# Sprite_CC1310_Development.net
KiCad netlist of a schematic drawn in EAGLE
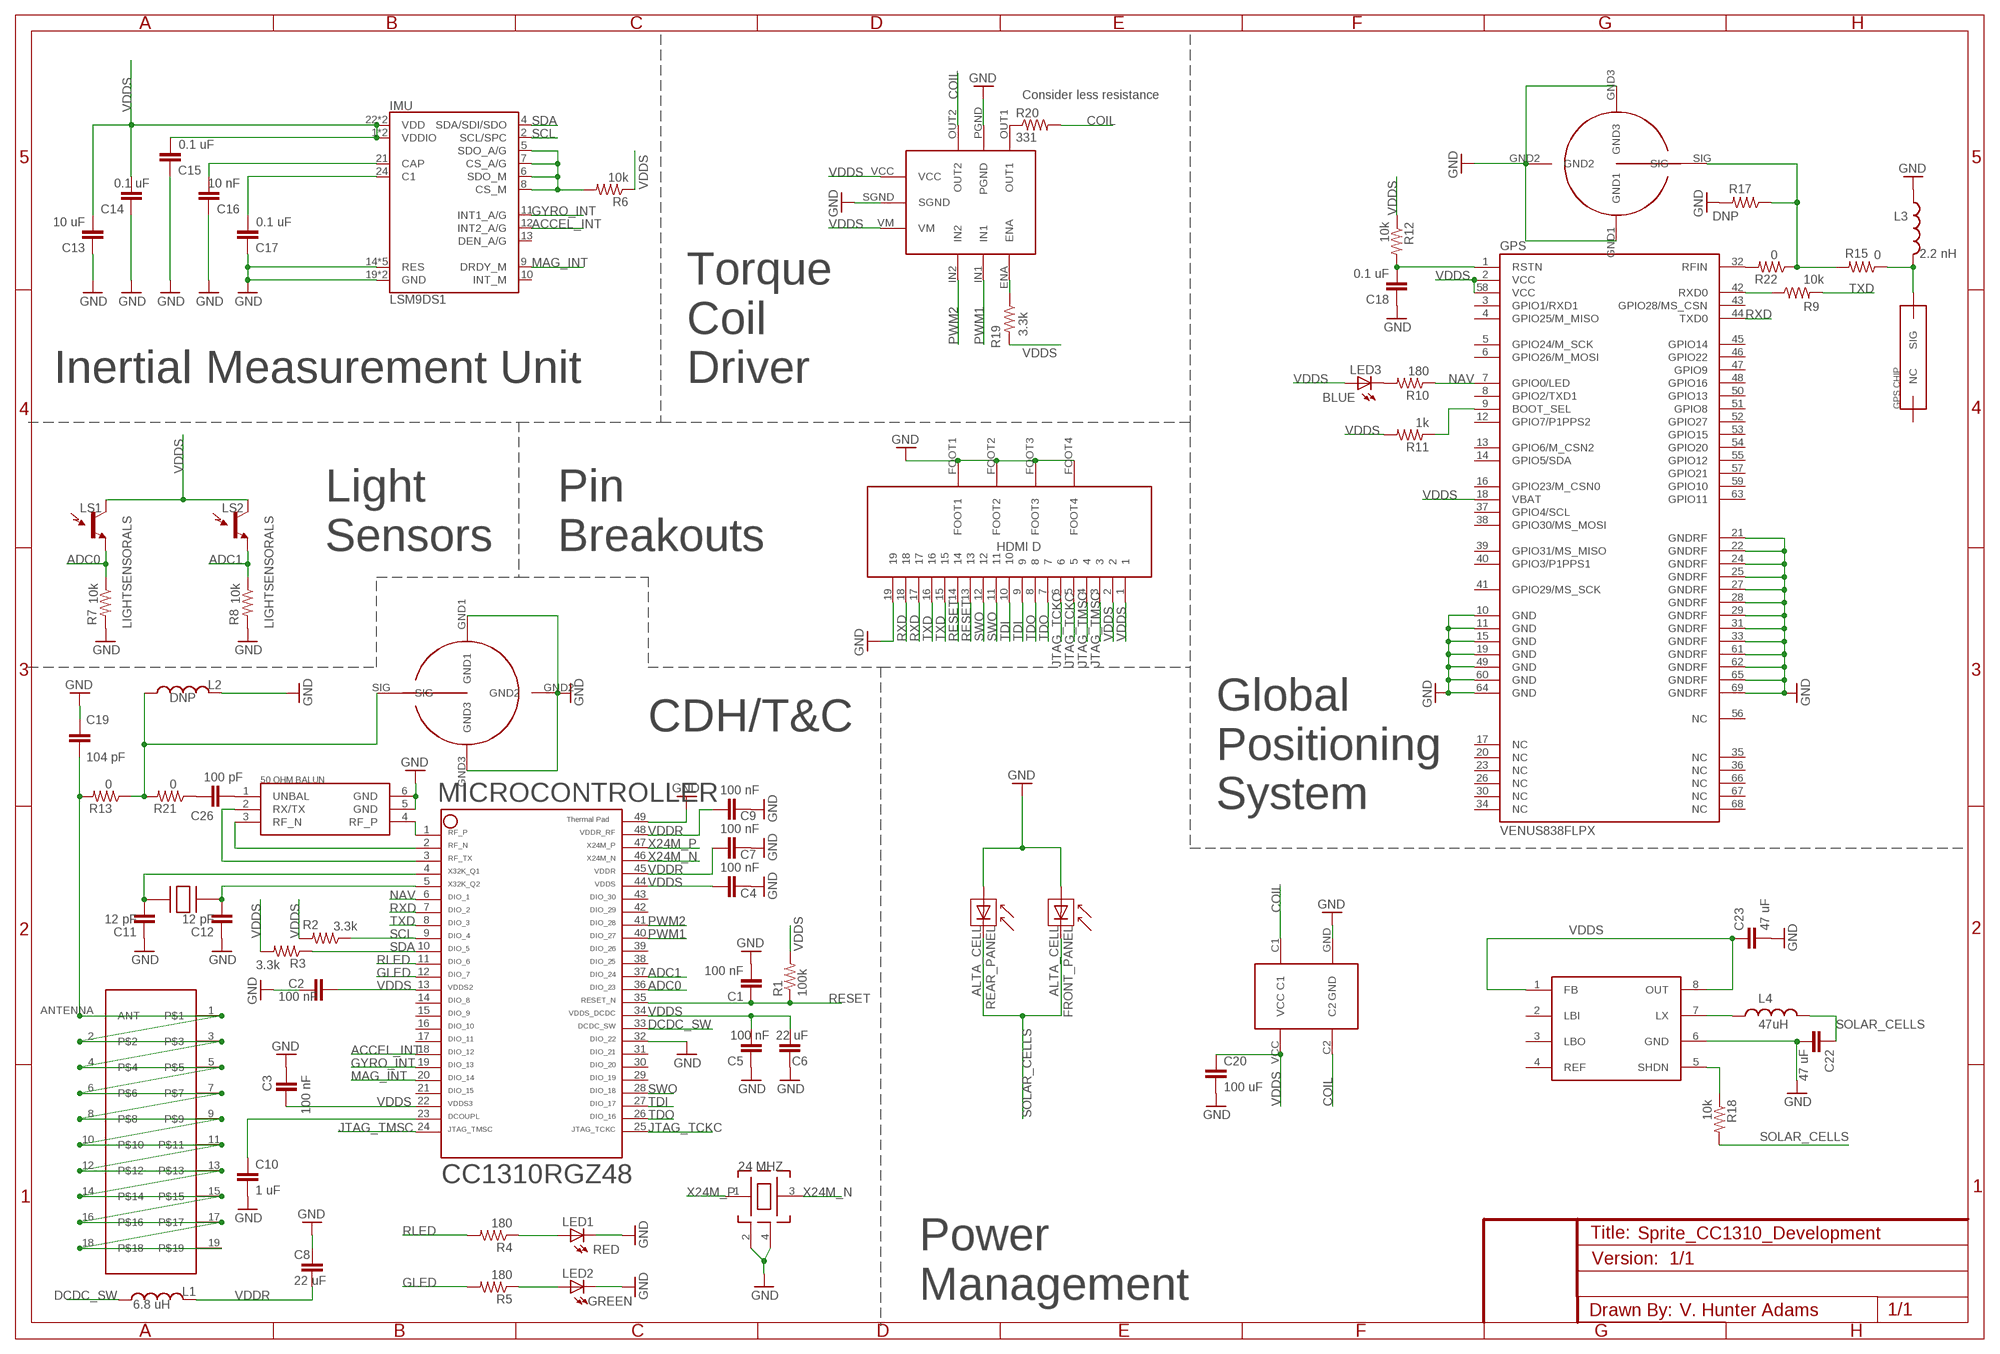
[diagram p0: schematic, sheet 1]

(export (version "E")
  (design (tool "Eeschema 10.0.6"))
  (components
    (comp (ref "32.768")
      (value "FC-135")
      (footprint "eagle-import:FC-135")
      (libsource (lib "eagle-import") (part "FC-135"))
    )
    (comp (ref "BALUN")
      (value "JOHANSON_BALUN")
      (footprint "eagle-import:JOHANSON_BALUN")
      (libsource (lib "eagle-import") (part "JOHANSON_BALUN"))
    )
    (comp (ref "C1")
      (value "100 nF")
      (footprint "eagle-import:0402-CAP")
      (libsource (lib "eagle-import") (part "CAP0402-CAP"))
    )
    (comp (ref "C2")
      (value "100 nF")
      (footprint "eagle-import:0402-CAP")
      (libsource (lib "eagle-import") (part "CAP0402-CAP"))
    )
    (comp (ref "C3")
      (value "100 nF")
      (footprint "eagle-import:0402-CAP")
      (libsource (lib "eagle-import") (part "CAP0402-CAP"))
    )
    (comp (ref "C4")
      (value "100 nF")
      (footprint "eagle-import:0402-CAP")
      (libsource (lib "eagle-import") (part "CAP0402-CAP"))
    )
    (comp (ref "C5")
      (value "100 nF")
      (footprint "eagle-import:0402-CAP")
      (libsource (lib "eagle-import") (part "CAP0402-CAP"))
    )
    (comp (ref "C6")
      (value "22 uF")
      (footprint "eagle-import:0402-CAP")
      (libsource (lib "eagle-import") (part "CAP0402-CAP"))
    )
    (comp (ref "C7")
      (value "100 nF")
      (footprint "eagle-import:0402-CAP")
      (libsource (lib "eagle-import") (part "CAP0402-CAP"))
    )
    (comp (ref "C8")
      (value "22 uF")
      (footprint "eagle-import:0402-CAP")
      (libsource (lib "eagle-import") (part "CAP0402-CAP"))
    )
    (comp (ref "C9")
      (value "100 nF")
      (footprint "eagle-import:0402-CAP")
      (libsource (lib "eagle-import") (part "CAP0402-CAP"))
    )
    (comp (ref "C10")
      (value "1 uF")
      (footprint "eagle-import:0402-CAP")
      (libsource (lib "eagle-import") (part "CAP0402-CAP"))
    )
    (comp (ref "C11")
      (value "12 pF")
      (footprint "eagle-import:0402-CAP")
      (libsource (lib "eagle-import") (part "CAP0402-CAP"))
    )
    (comp (ref "C12")
      (value "12 pF")
      (footprint "eagle-import:0402-CAP")
      (libsource (lib "eagle-import") (part "CAP0402-CAP"))
    )
    (comp (ref "C13")
      (value "10 uF")
      (footprint "eagle-import:0402-CAP")
      (libsource (lib "eagle-import") (part "CAP0402-CAP"))
    )
    (comp (ref "C14")
      (value "0.1 uF")
      (footprint "eagle-import:0402-CAP")
      (libsource (lib "eagle-import") (part "CAP0402-CAP"))
    )
    (comp (ref "C15")
      (value "0.1 uF")
      (footprint "eagle-import:0402-CAP")
      (libsource (lib "eagle-import") (part "CAP0402-CAP"))
    )
    (comp (ref "C16")
      (value "10 nF")
      (footprint "eagle-import:0402-CAP")
      (libsource (lib "eagle-import") (part "CAP0402-CAP"))
    )
    (comp (ref "C17")
      (value "0.1 uF")
      (footprint "eagle-import:0402-CAP")
      (libsource (lib "eagle-import") (part "CAP0402-CAP"))
    )
    (comp (ref "C18")
      (value "0.1 uF")
      (footprint "eagle-import:0402-CAP")
      (libsource (lib "eagle-import") (part "CAP0402-CAP"))
    )
    (comp (ref "C19")
      (value "104 pF")
      (footprint "eagle-import:0603-CAP")
      (libsource (lib "eagle-import") (part "CAP0603-CAP"))
    )
    (comp (ref "C20")
      (value "100 uF")
      (footprint "eagle-import:0805")
      (libsource (lib "eagle-import") (part "CAP0805"))
    )
    (comp (ref "C22")
      (value "47 uF")
      (footprint "eagle-import:0805")
      (libsource (lib "eagle-import") (part "CAP0805"))
    )
    (comp (ref "C23")
      (value "47 uF")
      (footprint "eagle-import:0805")
      (libsource (lib "eagle-import") (part "CAP0805"))
    )
    (comp (ref "C26")
      (value "100 pF")
      (footprint "eagle-import:0402-CAP")
      (libsource (lib "eagle-import") (part "CAP0402-CAP"))
    )
    (comp (ref "FRONT_PANEL")
      (value "ALTA_CELL")
      (footprint "eagle-import:ALTA_CELL")
      (libsource (lib "eagle-import") (part "ALTA_CELL"))
    )
    (comp (ref "GPS")
      (value "VENUS838FLPX")
      (footprint "eagle-import:VENUS838FLPX")
      (libsource (lib "eagle-import") (part "VENUS838FLPX"))
    )
    (comp (ref "IMU")
      (value "LSM9DS1")
      (footprint "eagle-import:LGA24-8X4")
      (libsource (lib "eagle-import") (part "LSM9DS1"))
    )
    (comp (ref "L1")
      (value "6.8 uH")
      (footprint "eagle-import:0603")
      (libsource (lib "eagle-import") (part "INDUCTOR0603"))
    )
    (comp (ref "L2")
      (value "DNP")
      (footprint "eagle-import:0603")
      (libsource (lib "eagle-import") (part "INDUCTOR0603"))
    )
    (comp (ref "L3")
      (value "2.2 nH")
      (footprint "eagle-import:0603")
      (libsource (lib "eagle-import") (part "INDUCTOR0603"))
    )
    (comp (ref "L4")
      (value "47uH")
      (footprint "eagle-import:0603")
      (libsource (lib "eagle-import") (part "INDUCTOR0603"))
    )
    (comp (ref "LED1")
      (value "RED")
      (footprint "eagle-import:LED-0603")
      (libsource (lib "eagle-import") (part "LED0603"))
    )
    (comp (ref "LED2")
      (value "GREEN")
      (footprint "eagle-import:LED-0603")
      (libsource (lib "eagle-import") (part "LED0603"))
    )
    (comp (ref "LED3")
      (value "BLUE")
      (footprint "eagle-import:LED-0603")
      (libsource (lib "eagle-import") (part "LED0603"))
    )
    (comp (ref "LS1")
      (value "LIGHTSENSORALS")
      (footprint "eagle-import:ALS-PT19")
      (libsource (lib "eagle-import") (part "LIGHTSENSORALS"))
    )
    (comp (ref "LS2")
      (value "LIGHTSENSORALS")
      (footprint "eagle-import:ALS-PT19")
      (libsource (lib "eagle-import") (part "LIGHTSENSORALS"))
    )
    (comp (ref "MICROCONTROLLER")
      (value "CC1310")
      (footprint "eagle-import:CC1310")
      (libsource (lib "eagle-import") (part "CC1310"))
    )
    (comp (ref "R1")
      (value "100k")
      (footprint "eagle-import:0402-RES")
      (libsource (lib "eagle-import") (part "RESISTOR0402-RES"))
    )
    (comp (ref "R2")
      (value "3.3k")
      (footprint "eagle-import:0402-RES")
      (libsource (lib "eagle-import") (part "RESISTOR0402-RES"))
    )
    (comp (ref "R3")
      (value "3.3k")
      (footprint "eagle-import:0402-RES")
      (libsource (lib "eagle-import") (part "RESISTOR0402-RES"))
    )
    (comp (ref "R4")
      (value "180")
      (footprint "eagle-import:0402-RES")
      (libsource (lib "eagle-import") (part "RESISTOR0402-RES"))
    )
    (comp (ref "R5")
      (value "180")
      (footprint "eagle-import:0402-RES")
      (libsource (lib "eagle-import") (part "RESISTOR0402-RES"))
    )
    (comp (ref "R6")
      (value "10k")
      (footprint "eagle-import:0402-RES")
      (libsource (lib "eagle-import") (part "RESISTOR0402-RES"))
    )
    (comp (ref "R7")
      (value "10k")
      (footprint "eagle-import:0402-RES")
      (libsource (lib "eagle-import") (part "RESISTOR0402-RES"))
    )
    (comp (ref "R8")
      (value "10k")
      (footprint "eagle-import:0402-RES")
      (libsource (lib "eagle-import") (part "RESISTOR0402-RES"))
    )
    (comp (ref "R9")
      (value "10k")
      (footprint "eagle-import:0402-RES")
      (libsource (lib "eagle-import") (part "RESISTOR0402-RES"))
    )
    (comp (ref "R10")
      (value "180")
      (footprint "eagle-import:0402-RES")
      (libsource (lib "eagle-import") (part "RESISTOR0402-RES"))
    )
    (comp (ref "R11")
      (value "1k")
      (footprint "eagle-import:0402-RES")
      (libsource (lib "eagle-import") (part "RESISTOR0402-RES"))
    )
    (comp (ref "R12")
      (value "10k")
      (footprint "eagle-import:0402-RES")
      (libsource (lib "eagle-import") (part "RESISTOR0402-RES"))
    )
    (comp (ref "R13")
      (value "0")
      (footprint "eagle-import:0603-RES")
      (libsource (lib "eagle-import") (part "RESISTOR0603-RES"))
    )
    (comp (ref "R15")
      (value "0")
      (footprint "eagle-import:0603-RES")
      (libsource (lib "eagle-import") (part "RESISTOR0603-RES"))
    )
    (comp (ref "R17")
      (value "DNP")
      (footprint "eagle-import:0603-RES")
      (libsource (lib "eagle-import") (part "RESISTOR0603-RES"))
    )
    (comp (ref "R18")
      (value "10k")
      (footprint "eagle-import:0402-RES")
      (libsource (lib "eagle-import") (part "RESISTOR0402-RES"))
    )
    (comp (ref "R19")
      (value "3.3k")
      (footprint "eagle-import:0402-RES")
      (libsource (lib "eagle-import") (part "RESISTOR0402-RES"))
    )
    (comp (ref "R20")
      (value "331")
      (footprint "eagle-import:0402-RES")
      (libsource (lib "eagle-import") (part "RESISTOR0402-RES"))
    )
    (comp (ref "R21")
      (value "0")
      (footprint "eagle-import:0603-RES")
      (libsource (lib "eagle-import") (part "RESISTOR0603-RES"))
    )
    (comp (ref "R22")
      (value "0")
      (footprint "eagle-import:0603-RES")
      (libsource (lib "eagle-import") (part "RESISTOR0603-RES"))
    )
    (comp (ref "REAR_PANEL")
      (value "ALTA_CELL")
      (footprint "eagle-import:ALTA_CELL")
      (libsource (lib "eagle-import") (part "ALTA_CELL"))
    )
    (comp (ref "TSX3225")
      (value "TSX-3225")
      (footprint "eagle-import:TSX-3225")
      (libsource (lib "eagle-import") (part "TSX-3225"))
    )
    (comp (ref "U$1")
      (value "HDMID")
      (footprint "eagle-import:HDMID")
      (libsource (lib "eagle-import") (part "HDMID"))
    )
    (comp (ref "U$2")
      (value "LV8417CS")
      (footprint "eagle-import:LV8417CS")
      (libsource (lib "eagle-import") (part "LV8417CS"))
    )
    (comp (ref "U$3")
      (value "MM5329-2700")
      (footprint "eagle-import:MM5829-2700")
      (libsource (lib "eagle-import") (part "MM5329-2700"))
    )
    (comp (ref "U$4")
      (value "PANASONIC_RECTIFIER")
      (footprint "eagle-import:PANASONIC_RECTIFIER")
      (libsource (lib "eagle-import") (part "PANASONIC_RECTIFIER"))
    )
    (comp (ref "U$5")
      (value "JOHANSON_GPS_CHIP")
      (footprint "eagle-import:JOHANSON_GPS_CHIP")
      (libsource (lib "eagle-import") (part "JOHANSON_GPS_CHIP"))
    )
    (comp (ref "U$6")
      (value "PCB_ANTENNA")
      (footprint "eagle-import:PCB_ANTENNA")
      (libsource (lib "eagle-import") (part "PCB_ANTENNA"))
    )
    (comp (ref "U$7")
      (value "MM5329-2700")
      (footprint "eagle-import:MM5829-2700")
      (libsource (lib "eagle-import") (part "MM5329-2700"))
    )
    (comp (ref "U$8")
      (value "L6920")
      (footprint "eagle-import:L6920")
      (libsource (lib "eagle-import") (part "L6920"))
    )
  )
  (nets
    (net (code "1") (name "/ACCEL_INT") (class "Default")
      (node (ref "IMU") (pin "12") (pinfunction "INT2_A/G_12") (pintype "bidirectional"))
      (node (ref "MICROCONTROLLER") (pin "18") (pinfunction "18_18") (pintype "bidirectional"))
    )
    (net (code "2") (name "/ADC0") (class "Default")
      (node (ref "LS1") (pin "E") (pinfunction "E1_E") (pintype "passive"))
      (node (ref "MICROCONTROLLER") (pin "36") (pinfunction "36_36") (pintype "bidirectional"))
      (node (ref "R7") (pin "1") (pinfunction "1_1") (pintype "passive"))
    )
    (net (code "3") (name "/ADC1") (class "Default")
      (node (ref "LS2") (pin "E") (pinfunction "E1_E") (pintype "passive"))
      (node (ref "MICROCONTROLLER") (pin "37") (pinfunction "37_37") (pintype "bidirectional"))
      (node (ref "R8") (pin "1") (pinfunction "1_1") (pintype "passive"))
    )
    (net (code "4") (name "/COIL") (class "Default")
      (node (ref "R20") (pin "2") (pinfunction "2_2") (pintype "passive"))
      (node (ref "U$2") (pin "OUT2") (pinfunction "OUT2_OUT2") (pintype "bidirectional"))
      (node (ref "U$4") (pin "C1") (pinfunction "C1_C1") (pintype "bidirectional"))
      (node (ref "U$4") (pin "C2") (pinfunction "C2_C2") (pintype "bidirectional"))
    )
    (net (code "5") (name "/DCDC_SW") (class "Default")
      (node (ref "L1") (pin "1") (pinfunction "1_1") (pintype "passive"))
      (node (ref "MICROCONTROLLER") (pin "33") (pinfunction "33_33") (pintype "power_in"))
    )
    (net (code "6") (name "/GLED") (class "Default")
      (node (ref "MICROCONTROLLER") (pin "12") (pinfunction "12_12") (pintype "bidirectional"))
      (node (ref "R5") (pin "2") (pinfunction "2_2") (pintype "passive"))
    )
    (net (code "7") (name "/GYRO_INT") (class "Default")
      (node (ref "IMU") (pin "11") (pinfunction "INT1_A/G_11") (pintype "bidirectional"))
      (node (ref "MICROCONTROLLER") (pin "19") (pinfunction "19_19") (pintype "bidirectional"))
    )
    (net (code "8") (name "/JTAG_TCKC") (class "Default")
      (node (ref "MICROCONTROLLER") (pin "25") (pinfunction "25_25") (pintype "input"))
      (node (ref "U$1") (pin "5") (pinfunction "5_5") (pintype "bidirectional"))
      (node (ref "U$1") (pin "6") (pinfunction "6_6") (pintype "bidirectional"))
    )
    (net (code "9") (name "/JTAG_TMSC") (class "Default")
      (node (ref "MICROCONTROLLER") (pin "24") (pinfunction "24_24") (pintype "bidirectional"))
      (node (ref "U$1") (pin "3") (pinfunction "3_3") (pintype "bidirectional"))
      (node (ref "U$1") (pin "4") (pinfunction "4_4") (pintype "bidirectional"))
    )
    (net (code "10") (name "/MAG_INT") (class "Default")
      (node (ref "IMU") (pin "9") (pinfunction "DRDY_M_9") (pintype "bidirectional"))
      (node (ref "MICROCONTROLLER") (pin "20") (pinfunction "20_20") (pintype "bidirectional"))
    )
    (net (code "11") (name "/NAV") (class "Default")
      (node (ref "GPS") (pin "7") (pinfunction "GPIO0/LED_7") (pintype "bidirectional"))
      (node (ref "MICROCONTROLLER") (pin "6") (pinfunction "6_6") (pintype "bidirectional"))
      (node (ref "R10") (pin "1") (pinfunction "1_1") (pintype "passive"))
    )
    (net (code "12") (name "/PWM1") (class "Default")
      (node (ref "MICROCONTROLLER") (pin "40") (pinfunction "40_40") (pintype "bidirectional"))
      (node (ref "U$2") (pin "IN1") (pinfunction "IN1_IN1") (pintype "bidirectional"))
    )
    (net (code "13") (name "/PWM2") (class "Default")
      (node (ref "MICROCONTROLLER") (pin "41") (pinfunction "41_41") (pintype "bidirectional"))
      (node (ref "U$2") (pin "IN2") (pinfunction "IN2_IN2") (pintype "bidirectional"))
    )
    (net (code "14") (name "/RESET") (class "Default")
      (node (ref "C1") (pin "1") (pinfunction "1_1") (pintype "passive"))
      (node (ref "MICROCONTROLLER") (pin "35") (pinfunction "35_35") (pintype "input"))
      (node (ref "R1") (pin "1") (pinfunction "1_1") (pintype "passive"))
      (node (ref "U$1") (pin "13") (pinfunction "13_13") (pintype "bidirectional"))
      (node (ref "U$1") (pin "14") (pinfunction "14_14") (pintype "bidirectional"))
    )
    (net (code "15") (name "/RLED") (class "Default")
      (node (ref "MICROCONTROLLER") (pin "11") (pinfunction "11_11") (pintype "bidirectional"))
      (node (ref "R4") (pin "2") (pinfunction "2_2") (pintype "passive"))
    )
    (net (code "16") (name "/RXD") (class "Default")
      (node (ref "GPS") (pin "44") (pinfunction "TXD0_44") (pintype "bidirectional"))
      (node (ref "MICROCONTROLLER") (pin "7") (pinfunction "7_7") (pintype "bidirectional"))
      (node (ref "U$1") (pin "17") (pinfunction "17_17") (pintype "bidirectional"))
      (node (ref "U$1") (pin "18") (pinfunction "18_18") (pintype "bidirectional"))
    )
    (net (code "17") (name "/SCL") (class "Default")
      (node (ref "IMU") (pin "2") (pinfunction "SCL/SPC_2") (pintype "bidirectional"))
      (node (ref "MICROCONTROLLER") (pin "9") (pinfunction "9_9") (pintype "bidirectional"))
      (node (ref "R2") (pin "1") (pinfunction "1_1") (pintype "passive"))
    )
    (net (code "18") (name "/SDA") (class "Default")
      (node (ref "IMU") (pin "4") (pinfunction "SDA/SDI/SDO_4") (pintype "bidirectional"))
      (node (ref "MICROCONTROLLER") (pin "10") (pinfunction "10_10") (pintype "bidirectional"))
      (node (ref "R3") (pin "1") (pinfunction "1_1") (pintype "passive"))
    )
    (net (code "19") (name "/SOLAR_CELLS") (class "Default")
      (node (ref "C22") (pin "1") (pinfunction "1_1") (pintype "passive"))
      (node (ref "FRONT_PANEL") (pin "+") (pinfunction "+_+") (pintype "passive"))
      (node (ref "L4") (pin "2") (pinfunction "2_2") (pintype "passive"))
      (node (ref "R18") (pin "2") (pinfunction "2_2") (pintype "passive"))
      (node (ref "REAR_PANEL") (pin "+") (pinfunction "+_+") (pintype "passive"))
    )
    (net (code "20") (name "/SWO") (class "Default")
      (node (ref "MICROCONTROLLER") (pin "28") (pinfunction "28_28") (pintype "bidirectional"))
      (node (ref "U$1") (pin "11") (pinfunction "11_11") (pintype "bidirectional"))
      (node (ref "U$1") (pin "12") (pinfunction "12_12") (pintype "bidirectional"))
    )
    (net (code "21") (name "/TDI") (class "Default")
      (node (ref "MICROCONTROLLER") (pin "27") (pinfunction "27_27") (pintype "bidirectional"))
      (node (ref "U$1") (pin "10") (pinfunction "10_10") (pintype "bidirectional"))
      (node (ref "U$1") (pin "9") (pinfunction "9_9") (pintype "bidirectional"))
    )
    (net (code "22") (name "/TDO") (class "Default")
      (node (ref "MICROCONTROLLER") (pin "26") (pinfunction "26_26") (pintype "bidirectional"))
      (node (ref "U$1") (pin "7") (pinfunction "7_7") (pintype "bidirectional"))
      (node (ref "U$1") (pin "8") (pinfunction "8_8") (pintype "bidirectional"))
    )
    (net (code "23") (name "/TXD") (class "Default")
      (node (ref "MICROCONTROLLER") (pin "8") (pinfunction "8_8") (pintype "bidirectional"))
      (node (ref "R9") (pin "2") (pinfunction "2_2") (pintype "passive"))
      (node (ref "U$1") (pin "15") (pinfunction "15_15") (pintype "bidirectional"))
      (node (ref "U$1") (pin "16") (pinfunction "16_16") (pintype "bidirectional"))
    )
    (net (code "24") (name "/VDDR") (class "Default")
      (node (ref "C7") (pin "1") (pinfunction "1_1") (pintype "passive"))
      (node (ref "C8") (pin "1") (pinfunction "1_1") (pintype "passive"))
      (node (ref "C9") (pin "1") (pinfunction "1_1") (pintype "passive"))
      (node (ref "L1") (pin "2") (pinfunction "2_2") (pintype "passive"))
      (node (ref "MICROCONTROLLER") (pin "45") (pinfunction "45_45") (pintype "power_in"))
      (node (ref "MICROCONTROLLER") (pin "48") (pinfunction "48_48") (pintype "power_in"))
    )
    (net (code "25") (name "/VDDS") (class "Default")
      (node (ref "C13") (pin "1") (pinfunction "1_1") (pintype "passive"))
      (node (ref "C14") (pin "1") (pinfunction "1_1") (pintype "passive"))
      (node (ref "C15") (pin "1") (pinfunction "1_1") (pintype "passive"))
      (node (ref "C2") (pin "1") (pinfunction "1_1") (pintype "passive"))
      (node (ref "C20") (pin "1") (pinfunction "1_1") (pintype "passive"))
      (node (ref "C23") (pin "1") (pinfunction "1_1") (pintype "passive"))
      (node (ref "C3") (pin "1") (pinfunction "1_1") (pintype "passive"))
      (node (ref "C4") (pin "1") (pinfunction "1_1") (pintype "passive"))
      (node (ref "C5") (pin "1") (pinfunction "1_1") (pintype "passive"))
      (node (ref "C6") (pin "1") (pinfunction "1_1") (pintype "passive"))
      (node (ref "GPS") (pin "18") (pinfunction "VBAT_18") (pintype "bidirectional"))
      (node (ref "GPS") (pin "2") (pinfunction "VCC_2") (pintype "bidirectional"))
      (node (ref "GPS") (pin "58") (pinfunction "VCC_58") (pintype "bidirectional"))
      (node (ref "IMU") (pin "1") (pinfunction "VDDIO_1") (pintype "bidirectional"))
      (node (ref "IMU") (pin "22") (pinfunction "VDD_22") (pintype "bidirectional"))
      (node (ref "IMU") (pin "23") (pinfunction "VDD_23") (pintype "bidirectional"))
      (node (ref "IMU") (pin "3") (pinfunction "VDDIO_3") (pintype "bidirectional"))
      (node (ref "LED3") (pin "A") (pinfunction "A_A") (pintype "passive"))
      (node (ref "LS1") (pin "C") (pinfunction "C1_C") (pintype "passive"))
      (node (ref "LS2") (pin "C") (pinfunction "C1_C") (pintype "passive"))
      (node (ref "MICROCONTROLLER") (pin "13") (pinfunction "13_13") (pintype "bidirectional"))
      (node (ref "MICROCONTROLLER") (pin "22") (pinfunction "22_22") (pintype "power_in"))
      (node (ref "MICROCONTROLLER") (pin "34") (pinfunction "34_34") (pintype "power_in"))
      (node (ref "MICROCONTROLLER") (pin "44") (pinfunction "44_44") (pintype "power_in"))
      (node (ref "R1") (pin "2") (pinfunction "2_2") (pintype "passive"))
      (node (ref "R11") (pin "2") (pinfunction "2_2") (pintype "passive"))
      (node (ref "R12") (pin "1") (pinfunction "1_1") (pintype "passive"))
      (node (ref "R19") (pin "2") (pinfunction "2_2") (pintype "passive"))
      (node (ref "R2") (pin "2") (pinfunction "2_2") (pintype "passive"))
      (node (ref "R3") (pin "2") (pinfunction "2_2") (pintype "passive"))
      (node (ref "R6") (pin "1") (pinfunction "1_1") (pintype "passive"))
      (node (ref "U$1") (pin "1") (pinfunction "1_1") (pintype "bidirectional"))
      (node (ref "U$1") (pin "2") (pinfunction "2_2") (pintype "bidirectional"))
      (node (ref "U$2") (pin "VCC") (pinfunction "VCC_VCC") (pintype "bidirectional"))
      (node (ref "U$2") (pin "VM") (pinfunction "VM_VM") (pintype "bidirectional"))
      (node (ref "U$4") (pin "VCC") (pinfunction "VCC_VCC") (pintype "bidirectional"))
      (node (ref "U$8") (pin "1") (pinfunction "FB_1") (pintype "bidirectional"))
      (node (ref "U$8") (pin "8") (pinfunction "OUT_8") (pintype "bidirectional"))
    )
    (net (code "26") (name "/X24M_N") (class "Default")
      (node (ref "MICROCONTROLLER") (pin "46") (pinfunction "46_46") (pintype "bidirectional"))
      (node (ref "TSX3225") (pin "3") (pinfunction "3_3") (pintype "bidirectional"))
    )
    (net (code "27") (name "/X24M_P") (class "Default")
      (node (ref "MICROCONTROLLER") (pin "47") (pinfunction "47_47") (pintype "input"))
      (node (ref "TSX3225") (pin "1") (pinfunction "1_1") (pintype "bidirectional"))
    )
    (net (code "28") (name "GND") (class "Default")
      (node (ref "BALUN") (pin "5") (pinfunction "GND_5") (pintype "bidirectional"))
      (node (ref "BALUN") (pin "6") (pinfunction "GND_6") (pintype "bidirectional"))
      (node (ref "C1") (pin "2") (pinfunction "2_2") (pintype "passive"))
      (node (ref "C10") (pin "2") (pinfunction "2_2") (pintype "passive"))
      (node (ref "C11") (pin "2") (pinfunction "2_2") (pintype "passive"))
      (node (ref "C12") (pin "2") (pinfunction "2_2") (pintype "passive"))
      (node (ref "C13") (pin "2") (pinfunction "2_2") (pintype "passive"))
      (node (ref "C14") (pin "2") (pinfunction "2_2") (pintype "passive"))
      (node (ref "C15") (pin "2") (pinfunction "2_2") (pintype "passive"))
      (node (ref "C16") (pin "2") (pinfunction "2_2") (pintype "passive"))
      (node (ref "C17") (pin "2") (pinfunction "2_2") (pintype "passive"))
      (node (ref "C18") (pin "2") (pinfunction "2_2") (pintype "passive"))
      (node (ref "C19") (pin "1") (pinfunction "1_1") (pintype "passive"))
      (node (ref "C2") (pin "2") (pinfunction "2_2") (pintype "passive"))
      (node (ref "C20") (pin "2") (pinfunction "2_2") (pintype "passive"))
      (node (ref "C22") (pin "2") (pinfunction "2_2") (pintype "passive"))
      (node (ref "C23") (pin "2") (pinfunction "2_2") (pintype "passive"))
      (node (ref "C3") (pin "2") (pinfunction "2_2") (pintype "passive"))
      (node (ref "C4") (pin "2") (pinfunction "2_2") (pintype "passive"))
      (node (ref "C5") (pin "2") (pinfunction "2_2") (pintype "passive"))
      (node (ref "C6") (pin "2") (pinfunction "2_2") (pintype "passive"))
      (node (ref "C7") (pin "2") (pinfunction "2_2") (pintype "passive"))
      (node (ref "C8") (pin "2") (pinfunction "2_2") (pintype "passive"))
      (node (ref "C9") (pin "2") (pinfunction "2_2") (pintype "passive"))
      (node (ref "FRONT_PANEL") (pin "-") (pinfunction "-_-") (pintype "passive"))
      (node (ref "GPS") (pin "10") (pinfunction "GND_10") (pintype "bidirectional"))
      (node (ref "GPS") (pin "11") (pinfunction "GND_11") (pintype "bidirectional"))
      (node (ref "GPS") (pin "15") (pinfunction "GND_15") (pintype "bidirectional"))
      (node (ref "GPS") (pin "19") (pinfunction "GND_19") (pintype "bidirectional"))
      (node (ref "GPS") (pin "21") (pinfunction "GNDRF_21") (pintype "bidirectional"))
      (node (ref "GPS") (pin "22") (pinfunction "GNDRF_22") (pintype "bidirectional"))
      (node (ref "GPS") (pin "24") (pinfunction "GNDRF_24") (pintype "bidirectional"))
      (node (ref "GPS") (pin "25") (pinfunction "GNDRF_25") (pintype "bidirectional"))
      (node (ref "GPS") (pin "27") (pinfunction "GNDRF_27") (pintype "bidirectional"))
      (node (ref "GPS") (pin "28") (pinfunction "GNDRF_28") (pintype "bidirectional"))
      (node (ref "GPS") (pin "29") (pinfunction "GNDRF_29") (pintype "bidirectional"))
      (node (ref "GPS") (pin "31") (pinfunction "GNDRF_31") (pintype "bidirectional"))
      (node (ref "GPS") (pin "33") (pinfunction "GNDRF_33") (pintype "bidirectional"))
      (node (ref "GPS") (pin "49") (pinfunction "GND_49") (pintype "bidirectional"))
      (node (ref "GPS") (pin "60") (pinfunction "GND_60") (pintype "bidirectional"))
      (node (ref "GPS") (pin "61") (pinfunction "GNDRF_61") (pintype "bidirectional"))
      (node (ref "GPS") (pin "62") (pinfunction "GNDRF_62") (pintype "bidirectional"))
      (node (ref "GPS") (pin "64") (pinfunction "GND_64") (pintype "bidirectional"))
      (node (ref "GPS") (pin "65") (pinfunction "GNDRF_65") (pintype "bidirectional"))
      (node (ref "GPS") (pin "69") (pinfunction "GNDRF_69") (pintype "bidirectional"))
      (node (ref "IMU") (pin "14") (pinfunction "RES_14") (pintype "bidirectional"))
      (node (ref "IMU") (pin "15") (pinfunction "RES_15") (pintype "bidirectional"))
      (node (ref "IMU") (pin "16") (pinfunction "RES_16") (pintype "bidirectional"))
      (node (ref "IMU") (pin "17") (pinfunction "RES_17") (pintype "bidirectional"))
      (node (ref "IMU") (pin "18") (pinfunction "RES_18") (pintype "bidirectional"))
      (node (ref "IMU") (pin "19") (pinfunction "GND_19") (pintype "bidirectional"))
      (node (ref "IMU") (pin "20") (pinfunction "GND_20") (pintype "bidirectional"))
      (node (ref "L2") (pin "2") (pinfunction "2_2") (pintype "passive"))
      (node (ref "L3") (pin "1") (pinfunction "1_1") (pintype "passive"))
      (node (ref "LED1") (pin "C") (pinfunction "C_C") (pintype "passive"))
      (node (ref "LED2") (pin "C") (pinfunction "C_C") (pintype "passive"))
      (node (ref "MICROCONTROLLER") (pin "32") (pinfunction "32_32") (pintype "bidirectional"))
      (node (ref "MICROCONTROLLER") (pin "49") (pinfunction "49_49") (pintype "input"))
      (node (ref "R17") (pin "2") (pinfunction "2_2") (pintype "passive"))
      (node (ref "R7") (pin "2") (pinfunction "2_2") (pintype "passive"))
      (node (ref "R8") (pin "2") (pinfunction "2_2") (pintype "passive"))
      (node (ref "REAR_PANEL") (pin "-") (pinfunction "-_-") (pintype "passive"))
      (node (ref "TSX3225") (pin "2") (pinfunction "2_2") (pintype "bidirectional"))
      (node (ref "TSX3225") (pin "4") (pinfunction "4_4") (pintype "bidirectional"))
      (node (ref "U$1") (pin "19") (pinfunction "19_19") (pintype "bidirectional"))
      (node (ref "U$1") (pin "FOOT1") (pinfunction "FOOT1_FOOT1") (pintype "bidirectional"))
      (node (ref "U$1") (pin "FOOT2") (pinfunction "FOOT2_FOOT2") (pintype "bidirectional"))
      (node (ref "U$1") (pin "FOOT3") (pinfunction "FOOT3_FOOT3") (pintype "bidirectional"))
      (node (ref "U$1") (pin "FOOT4") (pinfunction "FOOT4_FOOT4") (pintype "bidirectional"))
      (node (ref "U$2") (pin "PGND") (pinfunction "PGND_PGND") (pintype "bidirectional"))
      (node (ref "U$2") (pin "SGND") (pinfunction "SGND_SGND") (pintype "bidirectional"))
      (node (ref "U$3") (pin "GND1") (pinfunction "GND1_GND1") (pintype "bidirectional"))
      (node (ref "U$3") (pin "GND2") (pinfunction "GND2_GND2") (pintype "bidirectional"))
      (node (ref "U$3") (pin "GND3") (pinfunction "GND3_GND3") (pintype "bidirectional"))
      (node (ref "U$4") (pin "GND") (pinfunction "GND_GND") (pintype "bidirectional"))
      (node (ref "U$7") (pin "GND1") (pinfunction "GND1_GND1") (pintype "bidirectional"))
      (node (ref "U$7") (pin "GND2") (pinfunction "GND2_GND2") (pintype "bidirectional"))
      (node (ref "U$7") (pin "GND3") (pinfunction "GND3_GND3") (pintype "bidirectional"))
      (node (ref "U$8") (pin "6") (pinfunction "GND_6") (pintype "bidirectional"))
    )
    (net (code "29") (name "Net-(32.768-PadP1)") (class "Default")
      (node (ref "32.768") (pin "P1") (pinfunction "P1_P1") (pintype "bidirectional"))
      (node (ref "C12") (pin "1") (pinfunction "1_1") (pintype "passive"))
      (node (ref "MICROCONTROLLER") (pin "5") (pinfunction "5_5") (pintype "bidirectional"))
    )
    (net (code "30") (name "Net-(32.768-PadP2)") (class "Default")
      (node (ref "32.768") (pin "P2") (pinfunction "P2_P2") (pintype "bidirectional"))
      (node (ref "C11") (pin "1") (pinfunction "1_1") (pintype "passive"))
      (node (ref "MICROCONTROLLER") (pin "4") (pinfunction "4_4") (pintype "bidirectional"))
    )
    (net (code "31") (name "Net-(BALUN-RF_N)") (class "Default")
      (node (ref "BALUN") (pin "3") (pinfunction "RF_N_3") (pintype "bidirectional"))
      (node (ref "MICROCONTROLLER") (pin "2") (pinfunction "2_2") (pintype "bidirectional"))
    )
    (net (code "32") (name "Net-(BALUN-RF_P)") (class "Default")
      (node (ref "BALUN") (pin "4") (pinfunction "RF_P_4") (pintype "bidirectional"))
      (node (ref "MICROCONTROLLER") (pin "1") (pinfunction "1_1") (pintype "bidirectional"))
    )
    (net (code "33") (name "Net-(BALUN-RX{slash}TX)") (class "Default")
      (node (ref "BALUN") (pin "2") (pinfunction "RX/TX_2") (pintype "bidirectional"))
      (node (ref "MICROCONTROLLER") (pin "3") (pinfunction "3_3") (pintype "bidirectional"))
    )
    (net (code "34") (name "Net-(BALUN-UNBAL)") (class "Default")
      (node (ref "BALUN") (pin "1") (pinfunction "UNBAL_1") (pintype "bidirectional"))
      (node (ref "C26") (pin "2") (pinfunction "2_2") (pintype "passive"))
    )
    (net (code "35") (name "Net-(C10-Pad1)") (class "Default")
      (node (ref "C10") (pin "1") (pinfunction "1_1") (pintype "passive"))
      (node (ref "MICROCONTROLLER") (pin "23") (pinfunction "23_23") (pintype "bidirectional"))
    )
    (net (code "36") (name "Net-(C26-Pad1)") (class "Default")
      (node (ref "C26") (pin "1") (pinfunction "1_1") (pintype "passive"))
      (node (ref "R21") (pin "1") (pinfunction "1_1") (pintype "passive"))
    )
    (net (code "37") (name "Net-(GPS-BOOT_SEL)") (class "Default")
      (node (ref "GPS") (pin "9") (pinfunction "BOOT_SEL_9") (pintype "bidirectional"))
      (node (ref "R11") (pin "1") (pinfunction "1_1") (pintype "passive"))
    )
    (net (code "38") (name "Net-(GPS-RFIN)") (class "Default")
      (node (ref "GPS") (pin "32") (pinfunction "RFIN_32") (pintype "bidirectional"))
      (node (ref "R22") (pin "2") (pinfunction "2_2") (pintype "passive"))
    )
    (net (code "39") (name "Net-(GPS-RSTN)") (class "Default")
      (node (ref "C18") (pin "1") (pinfunction "1_1") (pintype "passive"))
      (node (ref "GPS") (pin "1") (pinfunction "RSTN_1") (pintype "bidirectional"))
      (node (ref "R12") (pin "2") (pinfunction "2_2") (pintype "passive"))
    )
    (net (code "40") (name "Net-(GPS-RXD0)") (class "Default")
      (node (ref "GPS") (pin "42") (pinfunction "RXD0_42") (pintype "bidirectional"))
      (node (ref "R9") (pin "1") (pinfunction "1_1") (pintype "passive"))
    )
    (net (code "41") (name "Net-(IMU-C1)") (class "Default")
      (node (ref "C17") (pin "1") (pinfunction "1_1") (pintype "passive"))
      (node (ref "IMU") (pin "24") (pinfunction "C1_24") (pintype "bidirectional"))
    )
    (net (code "42") (name "Net-(IMU-CAP)") (class "Default")
      (node (ref "C16") (pin "1") (pinfunction "1_1") (pintype "passive"))
      (node (ref "IMU") (pin "21") (pinfunction "CAP_21") (pintype "bidirectional"))
    )
    (net (code "43") (name "Net-(IMU-CS_A{slash}G)") (class "Default")
      (node (ref "IMU") (pin "5") (pinfunction "SDO_A/G_5") (pintype "bidirectional"))
      (node (ref "IMU") (pin "6") (pinfunction "SDO_M_6") (pintype "bidirectional"))
      (node (ref "IMU") (pin "7") (pinfunction "CS_A/G_7") (pintype "bidirectional"))
      (node (ref "IMU") (pin "8") (pinfunction "CS_M_8") (pintype "bidirectional"))
      (node (ref "R6") (pin "2") (pinfunction "2_2") (pintype "passive"))
    )
    (net (code "44") (name "Net-(L2-Pad1)") (class "Default")
      (node (ref "L2") (pin "1") (pinfunction "1_1") (pintype "passive"))
      (node (ref "R13") (pin "1") (pinfunction "1_1") (pintype "passive"))
      (node (ref "R21") (pin "2") (pinfunction "2_2") (pintype "passive"))
      (node (ref "U$3") (pin "SIG") (pinfunction "SIG_SIG") (pintype "bidirectional"))
    )
    (net (code "45") (name "Net-(L3-Pad2)") (class "Default")
      (node (ref "L3") (pin "2") (pinfunction "2_2") (pintype "passive"))
      (node (ref "R15") (pin "1") (pinfunction "1_1") (pintype "passive"))
      (node (ref "U$5") (pin "SIG") (pinfunction "SIG_SIG") (pintype "bidirectional"))
    )
    (net (code "46") (name "Net-(LED1-PadA)") (class "Default")
      (node (ref "LED1") (pin "A") (pinfunction "A_A") (pintype "passive"))
      (node (ref "R4") (pin "1") (pinfunction "1_1") (pintype "passive"))
    )
    (net (code "47") (name "Net-(LED2-PadA)") (class "Default")
      (node (ref "LED2") (pin "A") (pinfunction "A_A") (pintype "passive"))
      (node (ref "R5") (pin "1") (pinfunction "1_1") (pintype "passive"))
    )
    (net (code "48") (name "Net-(LED3-PadC)") (class "Default")
      (node (ref "LED3") (pin "C") (pinfunction "C_C") (pintype "passive"))
      (node (ref "R10") (pin "2") (pinfunction "2_2") (pintype "passive"))
    )
    (net (code "49") (name "Net-(R15-Pad2)") (class "Default")
      (node (ref "R15") (pin "2") (pinfunction "2_2") (pintype "passive"))
      (node (ref "R17") (pin "1") (pinfunction "1_1") (pintype "passive"))
      (node (ref "R22") (pin "1") (pinfunction "1_1") (pintype "passive"))
      (node (ref "U$7") (pin "SIG") (pinfunction "SIG_SIG") (pintype "bidirectional"))
    )
    (net (code "50") (name "Net-(R19-Pad1)") (class "Default")
      (node (ref "R19") (pin "1") (pinfunction "1_1") (pintype "passive"))
      (node (ref "U$2") (pin "ENA") (pinfunction "ENA_ENA") (pintype "bidirectional"))
    )
    (net (code "51") (name "Net-(R20-Pad1)") (class "Default")
      (node (ref "R20") (pin "1") (pinfunction "1_1") (pintype "passive"))
      (node (ref "U$2") (pin "OUT1") (pinfunction "OUT1_OUT1") (pintype "bidirectional"))
    )
    (net (code "52") (name "Net-(U$6-ANT)") (class "Default")
      (node (ref "C19") (pin "2") (pinfunction "2_2") (pintype "passive"))
      (node (ref "R13") (pin "2") (pinfunction "2_2") (pintype "passive"))
      (node (ref "U$6") (pin "1") (pinfunction "P$1_1") (pintype "bidirectional"))
      (node (ref "U$6") (pin "10") (pinfunction "P$10_10") (pintype "bidirectional"))
      (node (ref "U$6") (pin "11") (pinfunction "P$11_11") (pintype "bidirectional"))
      (node (ref "U$6") (pin "12") (pinfunction "P$12_12") (pintype "bidirectional"))
      (node (ref "U$6") (pin "13") (pinfunction "P$13_13") (pintype "bidirectional"))
      (node (ref "U$6") (pin "14") (pinfunction "P$14_14") (pintype "bidirectional"))
      (node (ref "U$6") (pin "15") (pinfunction "P$15_15") (pintype "bidirectional"))
      (node (ref "U$6") (pin "16") (pinfunction "P$16_16") (pintype "bidirectional"))
      (node (ref "U$6") (pin "17") (pinfunction "P$17_17") (pintype "bidirectional"))
      (node (ref "U$6") (pin "18") (pinfunction "P$18_18") (pintype "bidirectional"))
      (node (ref "U$6") (pin "19") (pinfunction "P$19_19") (pintype "bidirectional"))
      (node (ref "U$6") (pin "2") (pinfunction "P$2_2") (pintype "bidirectional"))
      (node (ref "U$6") (pin "3") (pinfunction "P$3_3") (pintype "bidirectional"))
      (node (ref "U$6") (pin "4") (pinfunction "P$4_4") (pintype "bidirectional"))
      (node (ref "U$6") (pin "5") (pinfunction "P$5_5") (pintype "bidirectional"))
      (node (ref "U$6") (pin "6") (pinfunction "P$6_6") (pintype "bidirectional"))
      (node (ref "U$6") (pin "7") (pinfunction "P$7_7") (pintype "bidirectional"))
      (node (ref "U$6") (pin "8") (pinfunction "P$8_8") (pintype "bidirectional"))
      (node (ref "U$6") (pin "9") (pinfunction "P$9_9") (pintype "bidirectional"))
      (node (ref "U$6") (pin "ANTENNA") (pinfunction "ANT_ANTENNA") (pintype "bidirectional"))
    )
    (net (code "53") (name "Net-(U$8-LX)") (class "Default")
      (node (ref "L4") (pin "1") (pinfunction "1_1") (pintype "passive"))
      (node (ref "U$8") (pin "7") (pinfunction "LX_7") (pintype "bidirectional"))
    )
    (net (code "54") (name "Net-(U$8-SHDN)") (class "Default")
      (node (ref "R18") (pin "1") (pinfunction "1_1") (pintype "passive"))
      (node (ref "U$8") (pin "5") (pinfunction "SHDN_5") (pintype "bidirectional"))
    )
    (net (code "55") (name "unconnected-(GPS-GPIO1{slash}RXD1-Pad3)") (class "Default")
      (node (ref "GPS") (pin "3") (pinfunction "GPIO1/RXD1_3") (pintype "bidirectional"))
    )
    (net (code "56") (name "unconnected-(GPS-GPIO2{slash}TXD1-Pad8)") (class "Default")
      (node (ref "GPS") (pin "8") (pinfunction "GPIO2/TXD1_8") (pintype "bidirectional"))
    )
    (net (code "57") (name "unconnected-(GPS-GPIO3{slash}P1PPS1-Pad40)") (class "Default")
      (node (ref "GPS") (pin "40") (pinfunction "GPIO3/P1PPS1_40") (pintype "bidirectional"))
    )
    (net (code "58") (name "unconnected-(GPS-GPIO4{slash}SCL-Pad37)") (class "Default")
      (node (ref "GPS") (pin "37") (pinfunction "GPIO4/SCL_37") (pintype "bidirectional"))
    )
    (net (code "59") (name "unconnected-(GPS-GPIO5{slash}SDA-Pad14)") (class "Default")
      (node (ref "GPS") (pin "14") (pinfunction "GPIO5/SDA_14") (pintype "bidirectional"))
    )
    (net (code "60") (name "unconnected-(GPS-GPIO6{slash}M_CSN2-Pad13)") (class "Default")
      (node (ref "GPS") (pin "13") (pinfunction "GPIO6/M_CSN2_13") (pintype "bidirectional"))
    )
    (net (code "61") (name "unconnected-(GPS-GPIO7{slash}P1PPS2-Pad12)") (class "Default")
      (node (ref "GPS") (pin "12") (pinfunction "GPIO7/P1PPS2_12") (pintype "bidirectional"))
    )
    (net (code "62") (name "unconnected-(GPS-GPIO8-Pad51)") (class "Default")
      (node (ref "GPS") (pin "51") (pinfunction "GPIO8_51") (pintype "bidirectional"))
    )
    (net (code "63") (name "unconnected-(GPS-GPIO9-Pad47)") (class "Default")
      (node (ref "GPS") (pin "47") (pinfunction "GPIO9_47") (pintype "bidirectional"))
    )
    (net (code "64") (name "unconnected-(GPS-GPIO10-Pad59)") (class "Default")
      (node (ref "GPS") (pin "59") (pinfunction "GPIO10_59") (pintype "bidirectional"))
    )
    (net (code "65") (name "unconnected-(GPS-GPIO11-Pad63)") (class "Default")
      (node (ref "GPS") (pin "63") (pinfunction "GPIO11_63") (pintype "bidirectional"))
    )
    (net (code "66") (name "unconnected-(GPS-GPIO12-Pad55)") (class "Default")
      (node (ref "GPS") (pin "55") (pinfunction "GPIO12_55") (pintype "bidirectional"))
    )
    (net (code "67") (name "unconnected-(GPS-GPIO13-Pad50)") (class "Default")
      (node (ref "GPS") (pin "50") (pinfunction "GPIO13_50") (pintype "bidirectional"))
    )
    (net (code "68") (name "unconnected-(GPS-GPIO14-Pad45)") (class "Default")
      (node (ref "GPS") (pin "45") (pinfunction "GPIO14_45") (pintype "bidirectional"))
    )
    (net (code "69") (name "unconnected-(GPS-GPIO15-Pad53)") (class "Default")
      (node (ref "GPS") (pin "53") (pinfunction "GPIO15_53") (pintype "bidirectional"))
    )
    (net (code "70") (name "unconnected-(GPS-GPIO16-Pad48)") (class "Default")
      (node (ref "GPS") (pin "48") (pinfunction "GPIO16_48") (pintype "bidirectional"))
    )
    (net (code "71") (name "unconnected-(GPS-GPIO20-Pad54)") (class "Default")
      (node (ref "GPS") (pin "54") (pinfunction "GPIO20_54") (pintype "bidirectional"))
    )
    (net (code "72") (name "unconnected-(GPS-GPIO21-Pad57)") (class "Default")
      (node (ref "GPS") (pin "57") (pinfunction "GPIO21_57") (pintype "bidirectional"))
    )
    (net (code "73") (name "unconnected-(GPS-GPIO22-Pad46)") (class "Default")
      (node (ref "GPS") (pin "46") (pinfunction "GPIO22_46") (pintype "bidirectional"))
    )
    (net (code "74") (name "unconnected-(GPS-GPIO23{slash}M_CSN0-Pad16)") (class "Default")
      (node (ref "GPS") (pin "16") (pinfunction "GPIO23/M_CSN0_16") (pintype "bidirectional"))
    )
    (net (code "75") (name "unconnected-(GPS-GPIO24{slash}M_SCK-Pad5)") (class "Default")
      (node (ref "GPS") (pin "5") (pinfunction "GPIO24/M_SCK_5") (pintype "bidirectional"))
    )
    (net (code "76") (name "unconnected-(GPS-GPIO25{slash}M_MISO-Pad4)") (class "Default")
      (node (ref "GPS") (pin "4") (pinfunction "GPIO25/M_MISO_4") (pintype "bidirectional"))
    )
    (net (code "77") (name "unconnected-(GPS-GPIO26{slash}M_MOSI-Pad6)") (class "Default")
      (node (ref "GPS") (pin "6") (pinfunction "GPIO26/M_MOSI_6") (pintype "bidirectional"))
    )
    (net (code "78") (name "unconnected-(GPS-GPIO27-Pad52)") (class "Default")
      (node (ref "GPS") (pin "52") (pinfunction "GPIO27_52") (pintype "bidirectional"))
    )
    (net (code "79") (name "unconnected-(GPS-GPIO28{slash}MS_CSN-Pad43)") (class "Default")
      (node (ref "GPS") (pin "43") (pinfunction "GPIO28/MS_CSN_43") (pintype "bidirectional"))
    )
    (net (code "80") (name "unconnected-(GPS-GPIO29{slash}MS_SCK-Pad41)") (class "Default")
      (node (ref "GPS") (pin "41") (pinfunction "GPIO29/MS_SCK_41") (pintype "bidirectional"))
    )
    (net (code "81") (name "unconnected-(GPS-GPIO30{slash}MS_MOSI-Pad38)") (class "Default")
      (node (ref "GPS") (pin "38") (pinfunction "GPIO30/MS_MOSI_38") (pintype "bidirectional"))
    )
    (net (code "82") (name "unconnected-(GPS-GPIO31{slash}MS_MISO-Pad39)") (class "Default")
      (node (ref "GPS") (pin "39") (pinfunction "GPIO31/MS_MISO_39") (pintype "bidirectional"))
    )
    (net (code "83") (name "unconnected-(GPS-NC-Pad17)") (class "Default")
      (node (ref "GPS") (pin "17") (pinfunction "NC_17") (pintype "bidirectional"))
    )
    (net (code "84") (name "unconnected-(GPS-NC-Pad20)") (class "Default")
      (node (ref "GPS") (pin "20") (pinfunction "NC_20") (pintype "bidirectional"))
    )
    (net (code "85") (name "unconnected-(GPS-NC-Pad23)") (class "Default")
      (node (ref "GPS") (pin "23") (pinfunction "NC_23") (pintype "bidirectional"))
    )
    (net (code "86") (name "unconnected-(GPS-NC-Pad26)") (class "Default")
      (node (ref "GPS") (pin "26") (pinfunction "NC_26") (pintype "bidirectional"))
    )
    (net (code "87") (name "unconnected-(GPS-NC-Pad30)") (class "Default")
      (node (ref "GPS") (pin "30") (pinfunction "NC_30") (pintype "bidirectional"))
    )
    (net (code "88") (name "unconnected-(GPS-NC-Pad34)") (class "Default")
      (node (ref "GPS") (pin "34") (pinfunction "NC_34") (pintype "bidirectional"))
    )
    (net (code "89") (name "unconnected-(GPS-NC-Pad35)") (class "Default")
      (node (ref "GPS") (pin "35") (pinfunction "NC_35") (pintype "bidirectional"))
    )
    (net (code "90") (name "unconnected-(GPS-NC-Pad36)") (class "Default")
      (node (ref "GPS") (pin "36") (pinfunction "NC_36") (pintype "bidirectional"))
    )
    (net (code "91") (name "unconnected-(GPS-NC-Pad56)") (class "Default")
      (node (ref "GPS") (pin "56") (pinfunction "NC_56") (pintype "bidirectional"))
    )
    (net (code "92") (name "unconnected-(GPS-NC-Pad66)") (class "Default")
      (node (ref "GPS") (pin "66") (pinfunction "NC_66") (pintype "bidirectional"))
    )
    (net (code "93") (name "unconnected-(GPS-NC-Pad67)") (class "Default")
      (node (ref "GPS") (pin "67") (pinfunction "NC_67") (pintype "bidirectional"))
    )
    (net (code "94") (name "unconnected-(GPS-NC-Pad68)") (class "Default")
      (node (ref "GPS") (pin "68") (pinfunction "NC_68") (pintype "bidirectional"))
    )
    (net (code "95") (name "unconnected-(IMU-DEN_A{slash}G-Pad13)") (class "Default")
      (node (ref "IMU") (pin "13") (pinfunction "DEN_A/G_13") (pintype "bidirectional"))
    )
    (net (code "96") (name "unconnected-(IMU-INT_M-Pad10)") (class "Default")
      (node (ref "IMU") (pin "10") (pinfunction "INT_M_10") (pintype "bidirectional"))
    )
    (net (code "97") (name "unconnected-(MICROCONTROLLER-Pad14)") (class "Default")
      (node (ref "MICROCONTROLLER") (pin "14") (pinfunction "14_14") (pintype "bidirectional"))
    )
    (net (code "98") (name "unconnected-(MICROCONTROLLER-Pad15)") (class "Default")
      (node (ref "MICROCONTROLLER") (pin "15") (pinfunction "15_15") (pintype "bidirectional"))
    )
    (net (code "99") (name "unconnected-(MICROCONTROLLER-Pad16)") (class "Default")
      (node (ref "MICROCONTROLLER") (pin "16") (pinfunction "16_16") (pintype "bidirectional"))
    )
    (net (code "100") (name "unconnected-(MICROCONTROLLER-Pad17)") (class "Default")
      (node (ref "MICROCONTROLLER") (pin "17") (pinfunction "17_17") (pintype "bidirectional"))
    )
    (net (code "101") (name "unconnected-(MICROCONTROLLER-Pad21)") (class "Default")
      (node (ref "MICROCONTROLLER") (pin "21") (pinfunction "21_21") (pintype "bidirectional"))
    )
    (net (code "102") (name "unconnected-(MICROCONTROLLER-Pad29)") (class "Default")
      (node (ref "MICROCONTROLLER") (pin "29") (pinfunction "29_29") (pintype "bidirectional"))
    )
    (net (code "103") (name "unconnected-(MICROCONTROLLER-Pad30)") (class "Default")
      (node (ref "MICROCONTROLLER") (pin "30") (pinfunction "30_30") (pintype "bidirectional"))
    )
    (net (code "104") (name "unconnected-(MICROCONTROLLER-Pad31)") (class "Default")
      (node (ref "MICROCONTROLLER") (pin "31") (pinfunction "31_31") (pintype "bidirectional"))
    )
    (net (code "105") (name "unconnected-(MICROCONTROLLER-Pad38)") (class "Default")
      (node (ref "MICROCONTROLLER") (pin "38") (pinfunction "38_38") (pintype "bidirectional"))
    )
    (net (code "106") (name "unconnected-(MICROCONTROLLER-Pad39)") (class "Default")
      (node (ref "MICROCONTROLLER") (pin "39") (pinfunction "39_39") (pintype "input"))
    )
    (net (code "107") (name "unconnected-(MICROCONTROLLER-Pad42)") (class "Default")
      (node (ref "MICROCONTROLLER") (pin "42") (pinfunction "42_42") (pintype "bidirectional"))
    )
    (net (code "108") (name "unconnected-(MICROCONTROLLER-Pad43)") (class "Default")
      (node (ref "MICROCONTROLLER") (pin "43") (pinfunction "43_43") (pintype "bidirectional"))
    )
    (net (code "109") (name "unconnected-(U$5-PadNC)") (class "Default")
      (node (ref "U$5") (pin "NC") (pinfunction "NC_NC") (pintype "bidirectional"))
    )
    (net (code "110") (name "unconnected-(U$8-LBI-Pad2)") (class "Default")
      (node (ref "U$8") (pin "2") (pinfunction "LBI_2") (pintype "bidirectional"))
    )
    (net (code "111") (name "unconnected-(U$8-LBO-Pad3)") (class "Default")
      (node (ref "U$8") (pin "3") (pinfunction "LBO_3") (pintype "bidirectional"))
    )
    (net (code "112") (name "unconnected-(U$8-REF-Pad4)") (class "Default")
      (node (ref "U$8") (pin "4") (pinfunction "REF_4") (pintype "bidirectional"))
    )
  )
)
